# BMS_Master_eTable_RevC3.net
KiCad netlist of a schematic drawn in EAGLE
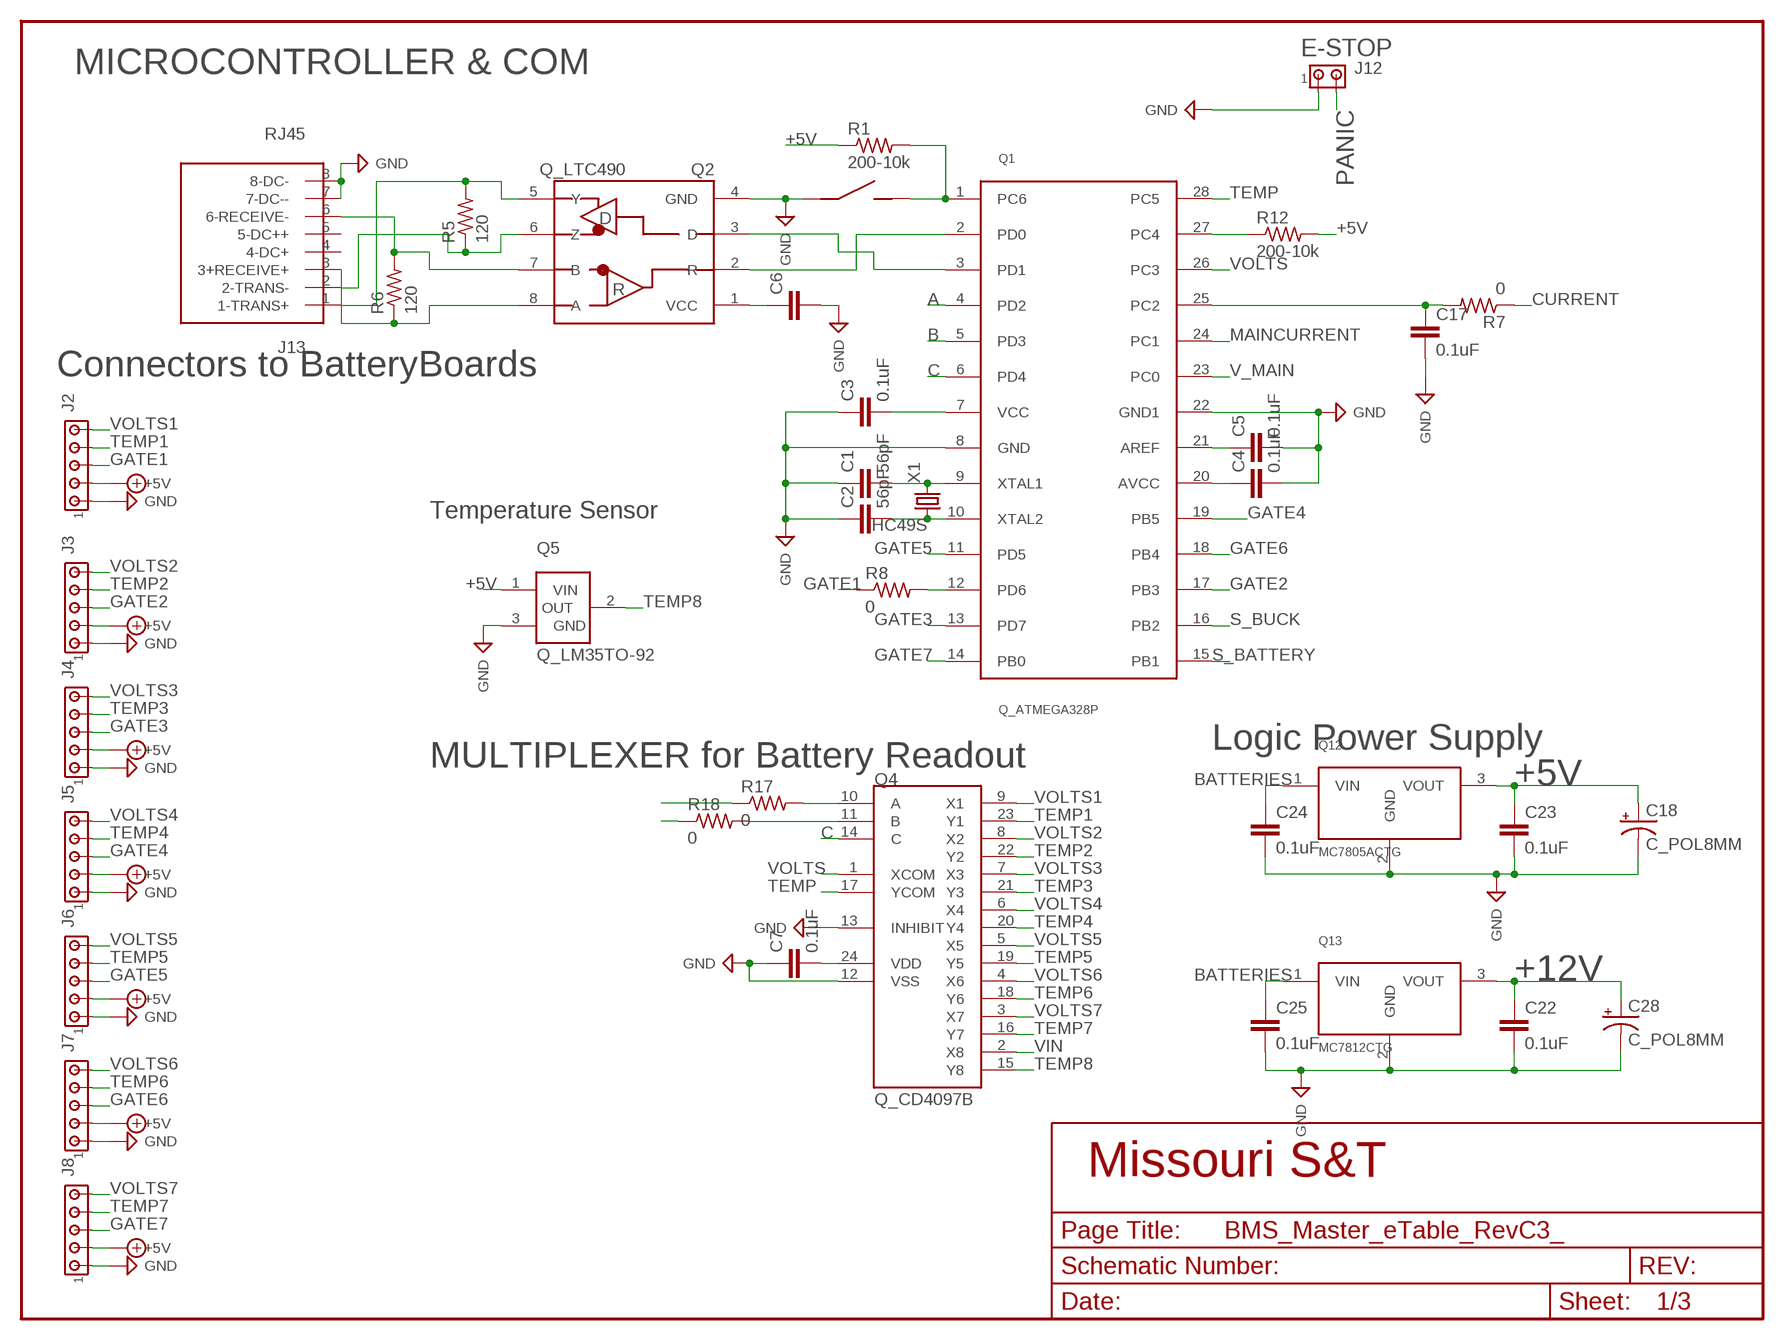
[diagram p0: schematic, sheet 1]
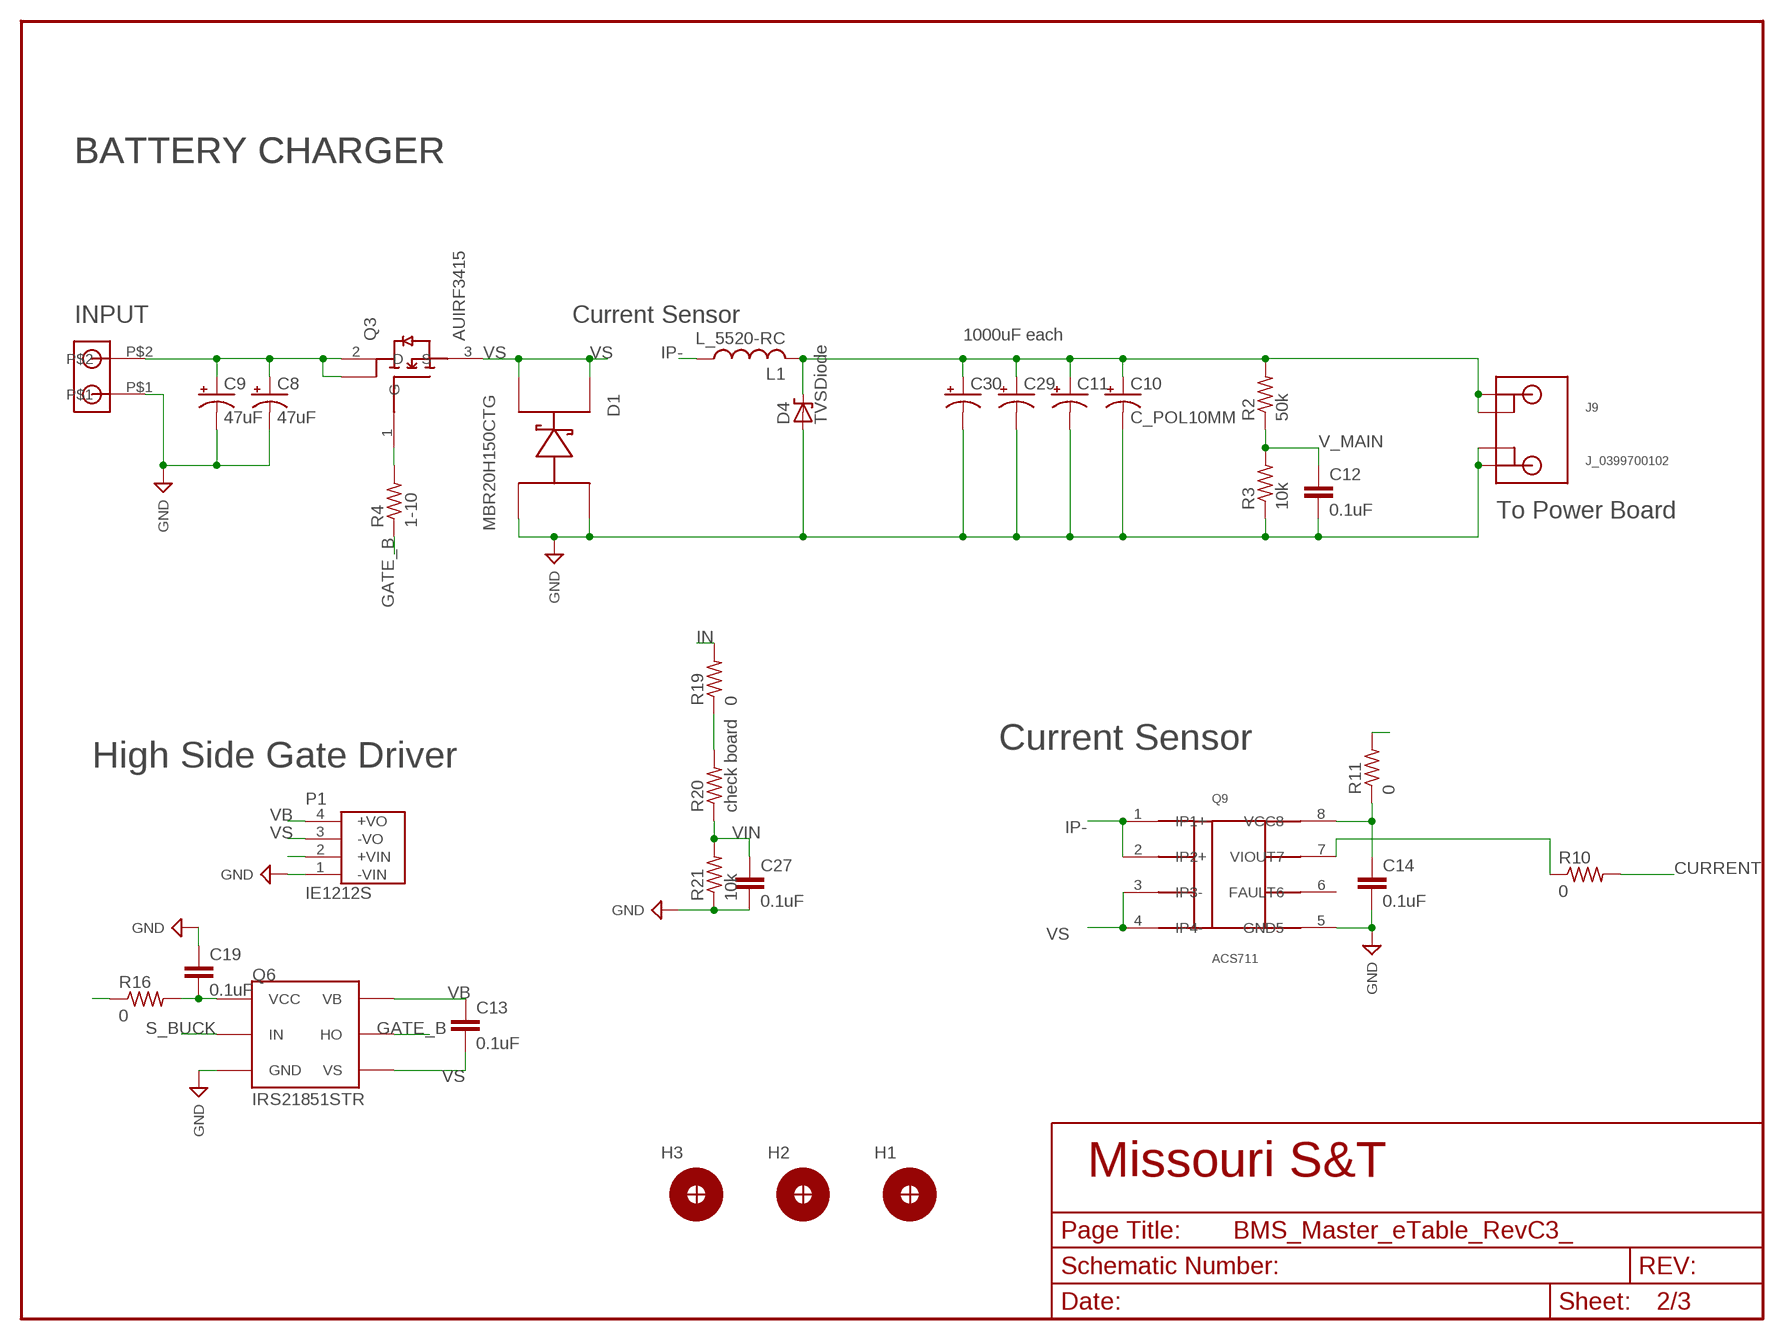
[diagram p1: schematic, sheet 2]
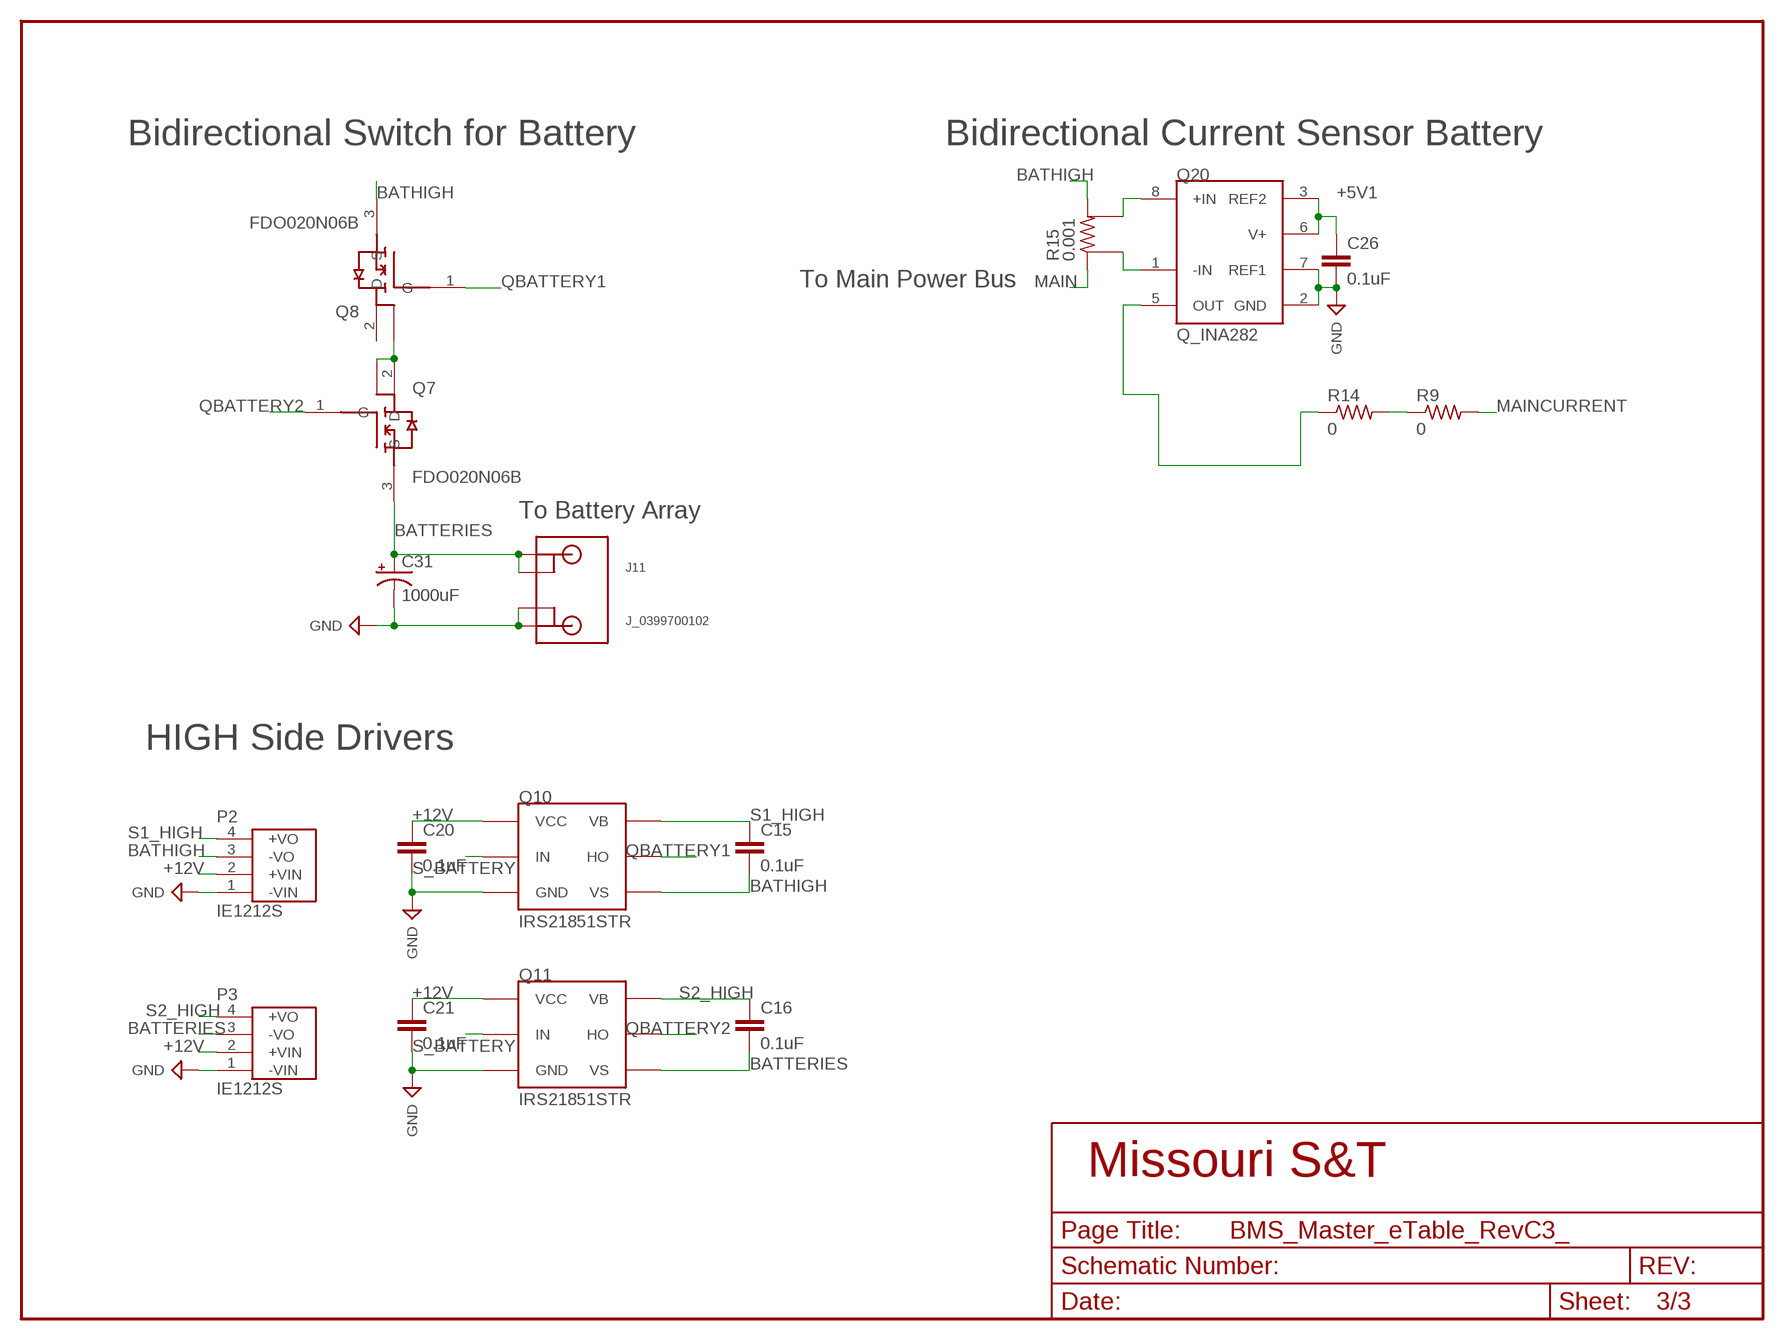
[diagram p2: schematic, sheet 3]

(export (version "E")
  (design (tool "Eeschema 10.0.6"))
  (components
    (comp (ref "C15")
      (value "0.1uF")
      (footprint "eagle-import:C_1206")
      (libsource (lib "eagle-import") (part "C_CAP_1206"))
    )
    (comp (ref "C16")
      (value "0.1uF")
      (footprint "eagle-import:C_1206")
      (libsource (lib "eagle-import") (part "C_CAP_1206"))
    )
    (comp (ref "C20")
      (value "0.1uF")
      (footprint "eagle-import:C_1206")
      (libsource (lib "eagle-import") (part "C_CAP_1206"))
    )
    (comp (ref "C21")
      (value "0.1uF")
      (footprint "eagle-import:C_1206")
      (libsource (lib "eagle-import") (part "C_CAP_1206"))
    )
    (comp (ref "C26")
      (value "0.1uF")
      (footprint "eagle-import:C_1206")
      (libsource (lib "eagle-import") (part "C_CAP_1206"))
    )
    (comp (ref "C31")
      (value "1000uF")
      (footprint "eagle-import:C_10MM")
      (libsource (lib "eagle-import") (part "C_POL10MM"))
    )
    (comp (ref "J11")
      (value "J_0399700102")
      (footprint "eagle-import:J_2CONHC")
      (libsource (lib "eagle-import") (part "J_0399700102"))
    )
    (comp (ref "P2")
      (value "IE1212S")
      (footprint "eagle-import:TME1215S")
      (libsource (lib "eagle-import") (part "TME1215S"))
    )
    (comp (ref "P3")
      (value "IE1212S")
      (footprint "eagle-import:TME1215S")
      (libsource (lib "eagle-import") (part "TME1215S"))
    )
    (comp (ref "Q7")
      (value "FDO020N06B")
      (footprint "eagle-import:TO-220-FLAT")
      (libsource (lib "eagle-import") (part "Q_CSD18532KCSPCB"))
    )
    (comp (ref "Q8")
      (value "FDO020N06B")
      (footprint "eagle-import:TO-220-FLAT")
      (libsource (lib "eagle-import") (part "Q_CSD18532KCSPCB"))
    )
    (comp (ref "Q10")
      (value "IRS21851STR")
      (footprint "eagle-import:SOIC8")
      (libsource (lib "eagle-import") (part "Q_IRS21851STR"))
    )
    (comp (ref "Q11")
      (value "IRS21851STR")
      (footprint "eagle-import:SOIC8")
      (libsource (lib "eagle-import") (part "Q_IRS21851STR"))
    )
    (comp (ref "Q20")
      (value "Q_INA282")
      (footprint "eagle-import:SOIC8")
      (libsource (lib "eagle-import") (part "Q_INA28"))
    )
    (comp (ref "R9")
      (value "0")
      (footprint "eagle-import:R_1_4W")
      (libsource (lib "eagle-import") (part "R_1/4W"))
    )
    (comp (ref "R14")
      (value "0")
      (footprint "eagle-import:R_1_4W")
      (libsource (lib "eagle-import") (part "R_1/4W"))
    )
    (comp (ref "R15")
      (value "0.001")
      (footprint "eagle-import:R_FC4L")
      (libsource (lib "eagle-import") (part "R_FC4L110R001JER"))
    )
    (comp (ref "C8")
      (value "47uF")
      (footprint "eagle-import:C_10MM")
      (libsource (lib "eagle-import") (part "C_POL10MM"))
    )
    (comp (ref "C9")
      (value "47uF")
      (footprint "eagle-import:C_10MM")
      (libsource (lib "eagle-import") (part "C_POL10MM"))
    )
    (comp (ref "C10")
      (value "C_POL10MM")
      (footprint "eagle-import:C_10MM")
      (libsource (lib "eagle-import") (part "C_POL10MM"))
    )
    (comp (ref "C11")
      (value "C_POL10MM")
      (footprint "eagle-import:C_10MM")
      (libsource (lib "eagle-import") (part "C_POL10MM"))
    )
    (comp (ref "C12")
      (value "0.1uF")
      (footprint "eagle-import:C_1206")
      (libsource (lib "eagle-import") (part "C_CAP_1206"))
    )
    (comp (ref "C13")
      (value "0.1uF")
      (footprint "eagle-import:C_1206")
      (libsource (lib "eagle-import") (part "C_CAP_1206"))
    )
    (comp (ref "C14")
      (value "0.1uF")
      (footprint "eagle-import:C_1206")
      (libsource (lib "eagle-import") (part "C_CAP_1206"))
    )
    (comp (ref "C19")
      (value "0.1uF")
      (footprint "eagle-import:C_1206")
      (libsource (lib "eagle-import") (part "C_CAP_1206"))
    )
    (comp (ref "C27")
      (value "0.1uF")
      (footprint "eagle-import:C_1206")
      (libsource (lib "eagle-import") (part "C_CAP_1206"))
    )
    (comp (ref "C29")
      (value "C_POL10MM")
      (footprint "eagle-import:C_10MM")
      (libsource (lib "eagle-import") (part "C_POL10MM"))
    )
    (comp (ref "C30")
      (value "C_POL10MM")
      (footprint "eagle-import:C_10MM")
      (libsource (lib "eagle-import") (part "C_POL10MM"))
    )
    (comp (ref "D1")
      (value "MBR20H150CTG")
      (footprint "eagle-import:TO-220-FLAT")
      (libsource (lib "eagle-import") (part "D_MBR20H150CTG"))
    )
    (comp (ref "D4")
      (value "TVSDiode")
      (footprint "eagle-import:DIODE_D3.5MM_LS15.24MM")
      (libsource (lib "eagle-import") (part "D_1.5KE480A_D3.5MM_LS15.24MM"))
    )
    (comp (ref "H1")
      (value "H_MNTHOLE_#6")
      (footprint "eagle-import:H_MNTHOLE_#6")
      (libsource (lib "eagle-import") (part "H_MNTHOLE_#6"))
    )
    (comp (ref "H2")
      (value "H_MNTHOLE_#6")
      (footprint "eagle-import:H_MNTHOLE_#6")
      (libsource (lib "eagle-import") (part "H_MNTHOLE_#6"))
    )
    (comp (ref "H3")
      (value "H_MNTHOLE_#6")
      (footprint "eagle-import:H_MNTHOLE_#6")
      (libsource (lib "eagle-import") (part "H_MNTHOLE_#6"))
    )
    (comp (ref "J9")
      (value "J_0399700102")
      (footprint "eagle-import:J_2CONHC")
      (libsource (lib "eagle-import") (part "J_0399700102"))
    )
    (comp (ref "J10")
      (value "J_1546074-2")
      (footprint "eagle-import:THERM_BLOCK_2")
      (libsource (lib "eagle-import") (part "J_1546074-2"))
    )
    (comp (ref "L1")
      (value "L_5520-RC")
      (footprint "eagle-import:L_5520-RC")
      (libsource (lib "eagle-import") (part "L_5520-RC"))
    )
    (comp (ref "P1")
      (value "IE1212S")
      (footprint "eagle-import:TME1215S")
      (libsource (lib "eagle-import") (part "TME1215S"))
    )
    (comp (ref "Q3")
      (value "AUIRF3415")
      (footprint "eagle-import:TO-220-FLAT")
      (libsource (lib "eagle-import") (part "Q_CSD18532KCSPCB"))
    )
    (comp (ref "Q6")
      (value "IRS21851STR")
      (footprint "eagle-import:SOIC8")
      (libsource (lib "eagle-import") (part "Q_IRS21851STR"))
    )
    (comp (ref "Q9")
      (value "ACS711")
      (footprint "eagle-import:Q_SO8")
      (libsource (lib "eagle-import") (part "Q_SO8ACS711"))
    )
    (comp (ref "R2")
      (value "50k")
      (footprint "eagle-import:R_1_4W")
      (libsource (lib "eagle-import") (part "R_1/4W"))
    )
    (comp (ref "R3")
      (value "10k")
      (footprint "eagle-import:R_1206")
      (libsource (lib "eagle-import") (part "R_RES_1206"))
    )
    (comp (ref "R4")
      (value "1-10")
      (footprint "eagle-import:R_1206")
      (libsource (lib "eagle-import") (part "Lib_Passive - Copy_R_RES_1206"))
    )
    (comp (ref "R10")
      (value "0")
      (footprint "eagle-import:R_1_4W")
      (libsource (lib "eagle-import") (part "R_1/4W"))
    )
    (comp (ref "R11")
      (value "0")
      (footprint "eagle-import:R_1_4W")
      (libsource (lib "eagle-import") (part "R_1/4W"))
    )
    (comp (ref "R16")
      (value "0")
      (footprint "eagle-import:R_1_4W")
      (libsource (lib "eagle-import") (part "R_1/4W"))
    )
    (comp (ref "R19")
      (value "0")
      (footprint "eagle-import:R_1_4W")
      (libsource (lib "eagle-import") (part "R_1/4W"))
    )
    (comp (ref "R20")
      (value "check board")
      (footprint "eagle-import:R_1_4W")
      (libsource (lib "eagle-import") (part "R_1/4W"))
    )
    (comp (ref "R21")
      (value "10k")
      (footprint "eagle-import:R_1206")
      (libsource (lib "eagle-import") (part "R_RES_1206"))
    )
    (comp (ref "C1")
      (value "56pF")
      (footprint "eagle-import:C_1206")
      (libsource (lib "eagle-import") (part "C_CAP_1206"))
    )
    (comp (ref "C2")
      (value "56pF")
      (footprint "eagle-import:C_1206")
      (libsource (lib "eagle-import") (part "C_CAP_1206"))
    )
    (comp (ref "C3")
      (value "0.1uF")
      (footprint "eagle-import:C_1206")
      (libsource (lib "eagle-import") (part "C_CAP_1206"))
    )
    (comp (ref "C4")
      (value "0.1uF")
      (footprint "eagle-import:C_1206")
      (libsource (lib "eagle-import") (part "C_CAP_1206"))
    )
    (comp (ref "C5")
      (value "0.1uF")
      (footprint "eagle-import:C_1206")
      (libsource (lib "eagle-import") (part "C_CAP_1206"))
    )
    (comp (ref "C6")
      (value "C_CAP_1206")
      (footprint "eagle-import:C_1206")
      (libsource (lib "eagle-import") (part "C_CAP_1206"))
    )
    (comp (ref "C7")
      (value "0.1uF")
      (footprint "eagle-import:C_1206")
      (libsource (lib "eagle-import") (part "C_CAP_1206"))
    )
    (comp (ref "C17")
      (value "0.1uF")
      (footprint "eagle-import:C_1206")
      (libsource (lib "eagle-import") (part "C_CAP_1206"))
    )
    (comp (ref "C18")
      (value "C_POL8MM")
      (footprint "eagle-import:C_8MM")
      (libsource (lib "eagle-import") (part "C_POL8MM"))
    )
    (comp (ref "C22")
      (value "0.1uF")
      (footprint "eagle-import:C_1206")
      (libsource (lib "eagle-import") (part "C_CAP_1206"))
    )
    (comp (ref "C23")
      (value "0.1uF")
      (footprint "eagle-import:C_1206")
      (libsource (lib "eagle-import") (part "C_CAP_1206"))
    )
    (comp (ref "C24")
      (value "0.1uF")
      (footprint "eagle-import:C_1206")
      (libsource (lib "eagle-import") (part "C_CAP_1206"))
    )
    (comp (ref "C25")
      (value "0.1uF")
      (footprint "eagle-import:C_1206")
      (libsource (lib "eagle-import") (part "C_CAP_1206"))
    )
    (comp (ref "C28")
      (value "C_POL8MM")
      (footprint "eagle-import:C_8MM")
      (libsource (lib "eagle-import") (part "C_POL8MM"))
    )
    (comp (ref "J1")
      (value "J_MC32857")
      (footprint "eagle-import:J_TOGGLE")
      (libsource (lib "eagle-import") (part "J_MC32857"))
    )
    (comp (ref "J2")
      (value "J_MTA5P_100")
      (footprint "eagle-import:J_MTA100_5P")
      (libsource (lib "eagle-import") (part "J_MTA5P_100"))
    )
    (comp (ref "J3")
      (value "J_MTA5P_100")
      (footprint "eagle-import:J_MTA100_5P")
      (libsource (lib "eagle-import") (part "J_MTA5P_100"))
    )
    (comp (ref "J4")
      (value "J_MTA5P_100")
      (footprint "eagle-import:J_MTA100_5P")
      (libsource (lib "eagle-import") (part "J_MTA5P_100"))
    )
    (comp (ref "J5")
      (value "J_MTA5P_100")
      (footprint "eagle-import:J_MTA100_5P")
      (libsource (lib "eagle-import") (part "J_MTA5P_100"))
    )
    (comp (ref "J6")
      (value "J_MTA5P_100")
      (footprint "eagle-import:J_MTA100_5P")
      (libsource (lib "eagle-import") (part "J_MTA5P_100"))
    )
    (comp (ref "J7")
      (value "J_MTA5P_100")
      (footprint "eagle-import:J_MTA100_5P")
      (libsource (lib "eagle-import") (part "J_MTA5P_100"))
    )
    (comp (ref "J8")
      (value "J_MTA5P_100")
      (footprint "eagle-import:J_MTA100_5P")
      (libsource (lib "eagle-import") (part "J_MTA5P_100"))
    )
    (comp (ref "J12")
      (value "J_MTA2P_100")
      (footprint "eagle-import:J_MTA100_2P")
      (libsource (lib "eagle-import") (part "J_MTA2P_100"))
    )
    (comp (ref "J13")
      (value "RJ45")
      (footprint "eagle-import:RJ45-CAT5E")
      (libsource (lib "eagle-import") (part "RJ45"))
    )
    (comp (ref "Q1")
      (value "Q_ATMEGA328P")
      (footprint "eagle-import:DIP28")
      (libsource (lib "eagle-import") (part "Q_ATMEGA328P"))
    )
    (comp (ref "Q2")
      (value "Q_LTC490")
      (footprint "eagle-import:DIP8")
      (libsource (lib "eagle-import") (part "Q_LTC490"))
    )
    (comp (ref "Q4")
      (value "Q_CD4097B")
      (footprint "eagle-import:WDIP24")
      (libsource (lib "eagle-import") (part "Q_CD4067BRIGHT"))
    )
    (comp (ref "Q5")
      (value "Q_LM35TO-92")
      (footprint "eagle-import:TO-92-3")
      (libsource (lib "eagle-import") (part "Q_LM35TO-92"))
    )
    (comp (ref "Q12")
      (value "MC7805ACTG")
      (footprint "eagle-import:TO-220")
      (libsource (lib "eagle-import") (part "Q_LDO"))
    )
    (comp (ref "Q13")
      (value "MC7812CTG")
      (footprint "eagle-import:TO-220")
      (libsource (lib "eagle-import") (part "Q_LDO"))
    )
    (comp (ref "R1")
      (value "200-10k")
      (footprint "eagle-import:R_1206")
      (libsource (lib "eagle-import") (part "R_RES_1206"))
    )
    (comp (ref "R5")
      (value "120")
      (footprint "eagle-import:R_1206")
      (libsource (lib "eagle-import") (part "Lib_Passive - Copy_R_RES_1206"))
    )
    (comp (ref "R6")
      (value "120")
      (footprint "eagle-import:R_1206")
      (libsource (lib "eagle-import") (part "Lib_Passive - Copy_R_RES_1206"))
    )
    (comp (ref "R7")
      (value "0")
      (footprint "eagle-import:R_1_4W")
      (libsource (lib "eagle-import") (part "R_1/4W"))
    )
    (comp (ref "R8")
      (value "0")
      (footprint "eagle-import:R_1_4W")
      (libsource (lib "eagle-import") (part "R_1/4W"))
    )
    (comp (ref "R12")
      (value "200-10k")
      (footprint "eagle-import:R_0805")
      (libsource (lib "eagle-import") (part "R_RES_0805"))
    )
    (comp (ref "R17")
      (value "0")
      (footprint "eagle-import:R_1_4W")
      (libsource (lib "eagle-import") (part "R_1/4W"))
    )
    (comp (ref "R18")
      (value "0")
      (footprint "eagle-import:R_1_4W")
      (libsource (lib "eagle-import") (part "R_1/4W"))
    )
    (comp (ref "X1")
      (value "HC49S")
      (footprint "eagle-import:HC-49")
      (libsource (lib "eagle-import") (part "X_HC49SCRYSTAL"))
    )
  )
  (nets
    (net (code "1") (name "+5V") (class "Default")
      (node (ref "C18") (pin "+") (pinfunction "+_+") (pintype "passive"))
      (node (ref "C23") (pin "1") (pinfunction "1_1") (pintype "passive"))
      (node (ref "C3") (pin "2") (pinfunction "2_2") (pintype "passive"))
      (node (ref "C4") (pin "1") (pinfunction "1_1") (pintype "passive"))
      (node (ref "C6") (pin "1") (pinfunction "1_1") (pintype "passive"))
      (node (ref "C7") (pin "2") (pinfunction "2_2") (pintype "passive"))
      (node (ref "J2") (pin "2") (pinfunction "2_2") (pintype "passive"))
      (node (ref "J3") (pin "2") (pinfunction "2_2") (pintype "passive"))
      (node (ref "J4") (pin "2") (pinfunction "2_2") (pintype "passive"))
      (node (ref "J5") (pin "2") (pinfunction "2_2") (pintype "passive"))
      (node (ref "J6") (pin "2") (pinfunction "2_2") (pintype "passive"))
      (node (ref "J7") (pin "2") (pinfunction "2_2") (pintype "passive"))
      (node (ref "J8") (pin "2") (pinfunction "2_2") (pintype "passive"))
      (node (ref "Q1") (pin "20") (pinfunction "AVCC_20") (pintype "bidirectional"))
      (node (ref "Q1") (pin "7") (pinfunction "VCC_7") (pintype "bidirectional"))
      (node (ref "Q12") (pin "3") (pinfunction "VOUT_3") (pintype "bidirectional"))
      (node (ref "Q2") (pin "1") (pinfunction "VCC_1") (pintype "bidirectional"))
      (node (ref "Q4") (pin "24") (pinfunction "VDD_24") (pintype "bidirectional"))
      (node (ref "Q5") (pin "1") (pinfunction "VIN_1") (pintype "bidirectional"))
      (node (ref "R1") (pin "1") (pinfunction "1_1") (pintype "passive"))
      (node (ref "R11") (pin "2") (pinfunction "2_2") (pintype "passive"))
      (node (ref "R12") (pin "2") (pinfunction "2_2") (pintype "passive"))
    )
    (net (code "2") (name "+5V1") (class "Default")
      (node (ref "C14") (pin "1") (pinfunction "1_1") (pintype "passive"))
      (node (ref "C26") (pin "1") (pinfunction "1_1") (pintype "passive"))
      (node (ref "Q20") (pin "3") (pinfunction "REF2_3") (pintype "bidirectional"))
      (node (ref "Q20") (pin "6") (pinfunction "V+_6") (pintype "bidirectional"))
      (node (ref "Q9") (pin "8") (pinfunction "VCC8_8") (pintype "bidirectional"))
      (node (ref "R11") (pin "1") (pinfunction "1_1") (pintype "passive"))
    )
    (net (code "3") (name "+12V") (class "Default")
      (node (ref "C20") (pin "1") (pinfunction "1_1") (pintype "passive"))
      (node (ref "C21") (pin "1") (pinfunction "1_1") (pintype "passive"))
      (node (ref "C22") (pin "1") (pinfunction "1_1") (pintype "passive"))
      (node (ref "C28") (pin "+") (pinfunction "+_+") (pintype "passive"))
      (node (ref "P2") (pin "2") (pinfunction "+VIN_2") (pintype "input"))
      (node (ref "P3") (pin "2") (pinfunction "+VIN_2") (pintype "input"))
      (node (ref "Q10") (pin "1") (pinfunction "VCC_1") (pintype "bidirectional"))
      (node (ref "Q11") (pin "1") (pinfunction "VCC_1") (pintype "bidirectional"))
      (node (ref "Q13") (pin "3") (pinfunction "VOUT_3") (pintype "bidirectional"))
      (node (ref "R16") (pin "1") (pinfunction "1_1") (pintype "passive"))
    )
    (net (code "4") (name "+12V1") (class "Default")
      (node (ref "C19") (pin "2") (pinfunction "2_2") (pintype "passive"))
      (node (ref "P1") (pin "2") (pinfunction "+VIN_2") (pintype "input"))
      (node (ref "Q6") (pin "1") (pinfunction "VCC_1") (pintype "bidirectional"))
      (node (ref "R16") (pin "2") (pinfunction "2_2") (pintype "passive"))
    )
    (net (code "5") (name "A") (class "Default")
      (node (ref "Q1") (pin "4") (pinfunction "PD2_4") (pintype "bidirectional"))
      (node (ref "R17") (pin "1") (pinfunction "1_1") (pintype "passive"))
    )
    (net (code "6") (name "B") (class "Default")
      (node (ref "Q1") (pin "5") (pinfunction "PD3_5") (pintype "bidirectional"))
      (node (ref "R18") (pin "1") (pinfunction "1_1") (pintype "passive"))
    )
    (net (code "7") (name "BATHIGH") (class "Default")
      (node (ref "C15") (pin "2") (pinfunction "2_2") (pintype "passive"))
      (node (ref "P2") (pin "3") (pinfunction "-VO_3") (pintype "output"))
      (node (ref "Q10") (pin "6") (pinfunction "VS_6") (pintype "bidirectional"))
      (node (ref "Q8") (pin "3") (pinfunction "S_3") (pintype "bidirectional"))
      (node (ref "R15") (pin "2") (pinfunction "2_2") (pintype "passive"))
    )
    (net (code "8") (name "BATTERIES") (class "Default")
      (node (ref "C16") (pin "2") (pinfunction "2_2") (pintype "passive"))
      (node (ref "C24") (pin "1") (pinfunction "1_1") (pintype "passive"))
      (node (ref "C25") (pin "1") (pinfunction "1_1") (pintype "passive"))
      (node (ref "C31") (pin "P$1") (pinfunction "+_P$1") (pintype "passive"))
      (node (ref "J11") (pin "PIN1-1") (pinfunction "1-1_PIN1-1") (pintype "bidirectional"))
      (node (ref "J11") (pin "PIN1-2") (pinfunction "1-2_PIN1-2") (pintype "bidirectional"))
      (node (ref "P3") (pin "3") (pinfunction "-VO_3") (pintype "output"))
      (node (ref "Q11") (pin "6") (pinfunction "VS_6") (pintype "bidirectional"))
      (node (ref "Q12") (pin "1") (pinfunction "VIN_1") (pintype "bidirectional"))
      (node (ref "Q13") (pin "1") (pinfunction "VIN_1") (pintype "bidirectional"))
      (node (ref "Q7") (pin "3") (pinfunction "S_3") (pintype "bidirectional"))
    )
    (net (code "9") (name "C") (class "Default")
      (node (ref "Q1") (pin "6") (pinfunction "PD4_6") (pintype "bidirectional"))
      (node (ref "Q4") (pin "14") (pinfunction "C_14") (pintype "bidirectional"))
    )
    (net (code "10") (name "CURRENT") (class "Default")
      (node (ref "R10") (pin "2") (pinfunction "2_2") (pintype "passive"))
      (node (ref "R7") (pin "1") (pinfunction "1_1") (pintype "passive"))
    )
    (net (code "11") (name "GATE1") (class "Default")
      (node (ref "J2") (pin "3") (pinfunction "3_3") (pintype "passive"))
      (node (ref "R8") (pin "1") (pinfunction "1_1") (pintype "passive"))
    )
    (net (code "12") (name "GATE2") (class "Default")
      (node (ref "J3") (pin "3") (pinfunction "3_3") (pintype "passive"))
      (node (ref "Q1") (pin "17") (pinfunction "PB3_17") (pintype "bidirectional"))
    )
    (net (code "13") (name "GATE3") (class "Default")
      (node (ref "J4") (pin "3") (pinfunction "3_3") (pintype "passive"))
      (node (ref "Q1") (pin "13") (pinfunction "PD7_13") (pintype "bidirectional"))
    )
    (net (code "14") (name "GATE4") (class "Default")
      (node (ref "J5") (pin "3") (pinfunction "3_3") (pintype "passive"))
      (node (ref "Q1") (pin "19") (pinfunction "PB5_19") (pintype "bidirectional"))
    )
    (net (code "15") (name "GATE5") (class "Default")
      (node (ref "J6") (pin "3") (pinfunction "3_3") (pintype "passive"))
      (node (ref "Q1") (pin "11") (pinfunction "PD5_11") (pintype "bidirectional"))
    )
    (net (code "16") (name "GATE6") (class "Default")
      (node (ref "J7") (pin "3") (pinfunction "3_3") (pintype "passive"))
      (node (ref "Q1") (pin "18") (pinfunction "PB4_18") (pintype "bidirectional"))
    )
    (net (code "17") (name "GATE7") (class "Default")
      (node (ref "J8") (pin "3") (pinfunction "3_3") (pintype "passive"))
      (node (ref "Q1") (pin "14") (pinfunction "PB0_14") (pintype "bidirectional"))
    )
    (net (code "18") (name "GATE_B") (class "Default")
      (node (ref "Q6") (pin "7") (pinfunction "HO_7") (pintype "bidirectional"))
      (node (ref "R4") (pin "1") (pinfunction "1_1") (pintype "passive"))
    )
    (net (code "19") (name "GND") (class "Default")
      (node (ref "C1") (pin "1") (pinfunction "1_1") (pintype "passive"))
      (node (ref "C10") (pin "P$2") (pinfunction "-_P$2") (pintype "passive"))
      (node (ref "C11") (pin "P$2") (pinfunction "-_P$2") (pintype "passive"))
      (node (ref "C12") (pin "2") (pinfunction "2_2") (pintype "passive"))
      (node (ref "C14") (pin "2") (pinfunction "2_2") (pintype "passive"))
      (node (ref "C17") (pin "2") (pinfunction "2_2") (pintype "passive"))
      (node (ref "C18") (pin "-") (pinfunction "-_-") (pintype "passive"))
      (node (ref "C19") (pin "1") (pinfunction "1_1") (pintype "passive"))
      (node (ref "C2") (pin "1") (pinfunction "1_1") (pintype "passive"))
      (node (ref "C20") (pin "2") (pinfunction "2_2") (pintype "passive"))
      (node (ref "C21") (pin "2") (pinfunction "2_2") (pintype "passive"))
      (node (ref "C22") (pin "2") (pinfunction "2_2") (pintype "passive"))
      (node (ref "C23") (pin "2") (pinfunction "2_2") (pintype "passive"))
      (node (ref "C24") (pin "2") (pinfunction "2_2") (pintype "passive"))
      (node (ref "C25") (pin "2") (pinfunction "2_2") (pintype "passive"))
      (node (ref "C26") (pin "2") (pinfunction "2_2") (pintype "passive"))
      (node (ref "C27") (pin "2") (pinfunction "2_2") (pintype "passive"))
      (node (ref "C28") (pin "-") (pinfunction "-_-") (pintype "passive"))
      (node (ref "C29") (pin "P$2") (pinfunction "-_P$2") (pintype "passive"))
      (node (ref "C3") (pin "1") (pinfunction "1_1") (pintype "passive"))
      (node (ref "C30") (pin "P$2") (pinfunction "-_P$2") (pintype "passive"))
      (node (ref "C31") (pin "P$2") (pinfunction "-_P$2") (pintype "passive"))
      (node (ref "C4") (pin "2") (pinfunction "2_2") (pintype "passive"))
      (node (ref "C5") (pin "2") (pinfunction "2_2") (pintype "passive"))
      (node (ref "C6") (pin "2") (pinfunction "2_2") (pintype "passive"))
      (node (ref "C7") (pin "1") (pinfunction "1_1") (pintype "passive"))
      (node (ref "C8") (pin "P$2") (pinfunction "-_P$2") (pintype "passive"))
      (node (ref "C9") (pin "P$2") (pinfunction "-_P$2") (pintype "passive"))
      (node (ref "D1") (pin "1") (pinfunction "A1_1") (pintype "bidirectional"))
      (node (ref "D1") (pin "3") (pinfunction "A2_3") (pintype "bidirectional"))
      (node (ref "D4") (pin "A") (pinfunction "A_A") (pintype "passive"))
      (node (ref "J1") (pin "P$1") (pinfunction "1_P$1") (pintype "bidirectional"))
      (node (ref "J10") (pin "P$1") (pinfunction "P$1_P$1") (pintype "bidirectional"))
      (node (ref "J11") (pin "PIN2-1") (pinfunction "2-1_PIN2-1") (pintype "bidirectional"))
      (node (ref "J11") (pin "PIN2-2") (pinfunction "2-2_PIN2-2") (pintype "bidirectional"))
      (node (ref "J12") (pin "1") (pinfunction "1_1") (pintype "passive"))
      (node (ref "J13") (pin "7") (pinfunction "7-DC--_7") (pintype "bidirectional"))
      (node (ref "J13") (pin "8") (pinfunction "8-DC-_8") (pintype "bidirectional"))
      (node (ref "J2") (pin "1") (pinfunction "1_1") (pintype "passive"))
      (node (ref "J3") (pin "1") (pinfunction "1_1") (pintype "passive"))
      (node (ref "J4") (pin "1") (pinfunction "1_1") (pintype "passive"))
      (node (ref "J5") (pin "1") (pinfunction "1_1") (pintype "passive"))
      (node (ref "J6") (pin "1") (pinfunction "1_1") (pintype "passive"))
      (node (ref "J7") (pin "1") (pinfunction "1_1") (pintype "passive"))
      (node (ref "J8") (pin "1") (pinfunction "1_1") (pintype "passive"))
      (node (ref "J9") (pin "PIN2-1") (pinfunction "2-1_PIN2-1") (pintype "bidirectional"))
      (node (ref "J9") (pin "PIN2-2") (pinfunction "2-2_PIN2-2") (pintype "bidirectional"))
      (node (ref "P1") (pin "1") (pinfunction "-VIN_1") (pintype "input"))
      (node (ref "P2") (pin "1") (pinfunction "-VIN_1") (pintype "input"))
      (node (ref "P3") (pin "1") (pinfunction "-VIN_1") (pintype "input"))
      (node (ref "Q1") (pin "22") (pinfunction "GND1_22") (pintype "bidirectional"))
      (node (ref "Q1") (pin "8") (pinfunction "GND_8") (pintype "bidirectional"))
      (node (ref "Q10") (pin "4") (pinfunction "GND_4") (pintype "bidirectional"))
      (node (ref "Q11") (pin "4") (pinfunction "GND_4") (pintype "bidirectional"))
      (node (ref "Q12") (pin "2") (pinfunction "GND_2") (pintype "bidirectional"))
      (node (ref "Q13") (pin "2") (pinfunction "GND_2") (pintype "bidirectional"))
      (node (ref "Q2") (pin "4") (pinfunction "GND_4") (pintype "bidirectional"))
      (node (ref "Q20") (pin "2") (pinfunction "GND_2") (pintype "bidirectional"))
      (node (ref "Q20") (pin "7") (pinfunction "REF1_7") (pintype "bidirectional"))
      (node (ref "Q4") (pin "12") (pinfunction "VSS_12") (pintype "bidirectional"))
      (node (ref "Q4") (pin "13") (pinfunction "INHIBIT_13") (pintype "bidirectional"))
      (node (ref "Q5") (pin "3") (pinfunction "GND_3") (pintype "bidirectional"))
      (node (ref "Q6") (pin "4") (pinfunction "GND_4") (pintype "bidirectional"))
      (node (ref "Q9") (pin "5") (pinfunction "GND5_5") (pintype "bidirectional"))
      (node (ref "R21") (pin "1") (pinfunction "1_1") (pintype "passive"))
      (node (ref "R3") (pin "1") (pinfunction "1_1") (pintype "passive"))
    )
    (net (code "20") (name "IN") (class "Default")
      (node (ref "C8") (pin "P$1") (pinfunction "+_P$1") (pintype "passive"))
      (node (ref "C9") (pin "P$1") (pinfunction "+_P$1") (pintype "passive"))
      (node (ref "J10") (pin "P$2") (pinfunction "P$2_P$2") (pintype "bidirectional"))
      (node (ref "Q3") (pin "2") (pinfunction "D_2") (pintype "bidirectional"))
      (node (ref "Q3") (pin "4") (pinfunction "P$1_4") (pintype "bidirectional"))
      (node (ref "R19") (pin "2") (pinfunction "2_2") (pintype "passive"))
    )
    (net (code "21") (name "IP-") (class "Default")
      (node (ref "L1") (pin "1") (pinfunction "1_1") (pintype "passive"))
      (node (ref "Q9") (pin "1") (pinfunction "IP1+_1") (pintype "bidirectional"))
      (node (ref "Q9") (pin "2") (pinfunction "IP2+_2") (pintype "bidirectional"))
    )
    (net (code "22") (name "MAIN") (class "Default")
      (node (ref "C10") (pin "P$1") (pinfunction "+_P$1") (pintype "passive"))
      (node (ref "C11") (pin "P$1") (pinfunction "+_P$1") (pintype "passive"))
      (node (ref "C29") (pin "P$1") (pinfunction "+_P$1") (pintype "passive"))
      (node (ref "C30") (pin "P$1") (pinfunction "+_P$1") (pintype "passive"))
      (node (ref "D4") (pin "C") (pinfunction "K_C") (pintype "passive"))
      (node (ref "J9") (pin "PIN1-1") (pinfunction "1-1_PIN1-1") (pintype "bidirectional"))
      (node (ref "J9") (pin "PIN1-2") (pinfunction "1-2_PIN1-2") (pintype "bidirectional"))
      (node (ref "L1") (pin "2") (pinfunction "2_2") (pintype "passive"))
      (node (ref "R15") (pin "1") (pinfunction "1_1") (pintype "passive"))
      (node (ref "R2") (pin "2") (pinfunction "2_2") (pintype "passive"))
    )
    (net (code "23") (name "MAINCURRENT") (class "Default")
      (node (ref "Q1") (pin "24") (pinfunction "PC1_24") (pintype "bidirectional"))
      (node (ref "R9") (pin "2") (pinfunction "2_2") (pintype "passive"))
    )
    (net (code "24") (name "Net-(J1-2)") (class "Default")
      (node (ref "J1") (pin "P$2") (pinfunction "2_P$2") (pintype "bidirectional"))
      (node (ref "Q1") (pin "1") (pinfunction "PC6_1") (pintype "bidirectional"))
      (node (ref "R1") (pin "2") (pinfunction "2_2") (pintype "passive"))
    )
    (net (code "25") (name "Net-(J13-1-TRANS+)") (class "Default")
      (node (ref "J13") (pin "1") (pinfunction "1-TRANS+_1") (pintype "bidirectional"))
      (node (ref "Q2") (pin "5") (pinfunction "Y_5") (pintype "bidirectional"))
      (node (ref "R5") (pin "2") (pinfunction "2_2") (pintype "passive"))
    )
    (net (code "26") (name "Net-(J13-2-TRANS-)") (class "Default")
      (node (ref "J13") (pin "2") (pinfunction "2-TRANS-_2") (pintype "bidirectional"))
      (node (ref "Q2") (pin "6") (pinfunction "Z_6") (pintype "bidirectional"))
      (node (ref "R5") (pin "1") (pinfunction "1_1") (pintype "passive"))
    )
    (net (code "27") (name "Net-(J13-3+RECEIVE+)") (class "Default")
      (node (ref "J13") (pin "3") (pinfunction "3+RECEIVE+_3") (pintype "bidirectional"))
      (node (ref "Q2") (pin "8") (pinfunction "A_8") (pintype "bidirectional"))
      (node (ref "R6") (pin "1") (pinfunction "1_1") (pintype "passive"))
    )
    (net (code "28") (name "Net-(J13-6-RECEIVE-)") (class "Default")
      (node (ref "J13") (pin "6") (pinfunction "6-RECEIVE-_6") (pintype "bidirectional"))
      (node (ref "Q2") (pin "7") (pinfunction "B_7") (pintype "bidirectional"))
      (node (ref "R6") (pin "2") (pinfunction "2_2") (pintype "passive"))
    )
    (net (code "29") (name "Net-(Q1-AREF)") (class "Default")
      (node (ref "C5") (pin "1") (pinfunction "1_1") (pintype "passive"))
      (node (ref "Q1") (pin "21") (pinfunction "AREF_21") (pintype "bidirectional"))
    )
    (net (code "30") (name "Net-(Q1-PC2)") (class "Default")
      (node (ref "C17") (pin "1") (pinfunction "1_1") (pintype "passive"))
      (node (ref "Q1") (pin "25") (pinfunction "PC2_25") (pintype "bidirectional"))
      (node (ref "R7") (pin "2") (pinfunction "2_2") (pintype "passive"))
    )
    (net (code "31") (name "Net-(Q1-PD0)") (class "Default")
      (node (ref "Q1") (pin "2") (pinfunction "PD0_2") (pintype "bidirectional"))
      (node (ref "Q2") (pin "2") (pinfunction "R_2") (pintype "bidirectional"))
    )
    (net (code "32") (name "Net-(Q1-PD1)") (class "Default")
      (node (ref "Q1") (pin "3") (pinfunction "PD1_3") (pintype "bidirectional"))
      (node (ref "Q2") (pin "3") (pinfunction "D_3") (pintype "bidirectional"))
    )
    (net (code "33") (name "Net-(Q1-PD6)") (class "Default")
      (node (ref "Q1") (pin "12") (pinfunction "PD6_12") (pintype "bidirectional"))
      (node (ref "R8") (pin "2") (pinfunction "2_2") (pintype "passive"))
    )
    (net (code "34") (name "Net-(Q1-XTAL1)") (class "Default")
      (node (ref "C1") (pin "2") (pinfunction "2_2") (pintype "passive"))
      (node (ref "Q1") (pin "9") (pinfunction "XTAL1_9") (pintype "bidirectional"))
      (node (ref "X1") (pin "P$2") (pinfunction "2_P$2") (pintype "passive"))
    )
    (net (code "35") (name "Net-(Q1-XTAL2)") (class "Default")
      (node (ref "C2") (pin "2") (pinfunction "2_2") (pintype "passive"))
      (node (ref "Q1") (pin "10") (pinfunction "XTAL2_10") (pintype "bidirectional"))
      (node (ref "X1") (pin "P$1") (pinfunction "1_P$1") (pintype "passive"))
    )
    (net (code "36") (name "Net-(Q3-G)") (class "Default")
      (node (ref "Q3") (pin "1") (pinfunction "G_1") (pintype "bidirectional"))
      (node (ref "R4") (pin "2") (pinfunction "2_2") (pintype "passive"))
    )
    (net (code "37") (name "Net-(Q4-A)") (class "Default")
      (node (ref "Q4") (pin "10") (pinfunction "A_10") (pintype "bidirectional"))
      (node (ref "R17") (pin "2") (pinfunction "2_2") (pintype "passive"))
    )
    (net (code "38") (name "Net-(Q4-B)") (class "Default")
      (node (ref "Q4") (pin "11") (pinfunction "B_11") (pintype "bidirectional"))
      (node (ref "R18") (pin "2") (pinfunction "2_2") (pintype "passive"))
    )
    (net (code "39") (name "Net-(Q7-D)") (class "Default")
      (node (ref "Q7") (pin "2") (pinfunction "D_2") (pintype "bidirectional"))
      (node (ref "Q7") (pin "4") (pinfunction "P$1_4") (pintype "bidirectional"))
      (node (ref "Q8") (pin "4") (pinfunction "P$1_4") (pintype "bidirectional"))
    )
    (net (code "40") (name "Net-(Q9-VIOUT7)") (class "Default")
      (node (ref "Q9") (pin "7") (pinfunction "VIOUT7_7") (pintype "bidirectional"))
      (node (ref "R10") (pin "1") (pinfunction "1_1") (pintype "passive"))
    )
    (net (code "41") (name "Net-(Q20-+IN)") (class "Default")
      (node (ref "Q20") (pin "8") (pinfunction "+IN_8") (pintype "bidirectional"))
      (node (ref "R15") (pin "SENSE2") (pinfunction "SENSE2_SENSE2") (pintype "bidirectional"))
    )
    (net (code "42") (name "Net-(Q20--IN)") (class "Default")
      (node (ref "Q20") (pin "1") (pinfunction "-IN_1") (pintype "bidirectional"))
      (node (ref "R15") (pin "SENSE1") (pinfunction "SENSE1_SENSE1") (pintype "bidirectional"))
    )
    (net (code "43") (name "Net-(Q20-OUT)") (class "Default")
      (node (ref "Q20") (pin "5") (pinfunction "OUT_5") (pintype "bidirectional"))
      (node (ref "R14") (pin "1") (pinfunction "1_1") (pintype "passive"))
    )
    (net (code "44") (name "Net-(R14-Pad2)") (class "Default")
      (node (ref "R14") (pin "2") (pinfunction "2_2") (pintype "passive"))
      (node (ref "R9") (pin "1") (pinfunction "1_1") (pintype "passive"))
    )
    (net (code "45") (name "Net-(R19-Pad1)") (class "Default")
      (node (ref "R19") (pin "1") (pinfunction "1_1") (pintype "passive"))
      (node (ref "R20") (pin "2") (pinfunction "2_2") (pintype "passive"))
    )
    (net (code "46") (name "PANIC") (class "Default")
      (node (ref "J12") (pin "2") (pinfunction "2_2") (pintype "passive"))
      (node (ref "Q1") (pin "27") (pinfunction "PC4_27") (pintype "bidirectional"))
      (node (ref "R12") (pin "1") (pinfunction "1_1") (pintype "passive"))
    )
    (net (code "47") (name "QBATTERY1") (class "Default")
      (node (ref "Q10") (pin "7") (pinfunction "HO_7") (pintype "bidirectional"))
      (node (ref "Q8") (pin "1") (pinfunction "G_1") (pintype "bidirectional"))
    )
    (net (code "48") (name "QBATTERY2") (class "Default")
      (node (ref "Q11") (pin "7") (pinfunction "HO_7") (pintype "bidirectional"))
      (node (ref "Q7") (pin "1") (pinfunction "G_1") (pintype "bidirectional"))
    )
    (net (code "49") (name "S1_HIGH") (class "Default")
      (node (ref "C15") (pin "1") (pinfunction "1_1") (pintype "passive"))
      (node (ref "P2") (pin "4") (pinfunction "+VO_4") (pintype "output"))
      (node (ref "Q10") (pin "8") (pinfunction "VB_8") (pintype "bidirectional"))
    )
    (net (code "50") (name "S2_HIGH") (class "Default")
      (node (ref "C16") (pin "1") (pinfunction "1_1") (pintype "passive"))
      (node (ref "P3") (pin "4") (pinfunction "+VO_4") (pintype "output"))
      (node (ref "Q11") (pin "8") (pinfunction "VB_8") (pintype "bidirectional"))
    )
    (net (code "51") (name "S_BATTERY") (class "Default")
      (node (ref "Q1") (pin "15") (pinfunction "PB1_15") (pintype "bidirectional"))
      (node (ref "Q10") (pin "2") (pinfunction "IN_2") (pintype "bidirectional"))
      (node (ref "Q11") (pin "2") (pinfunction "IN_2") (pintype "bidirectional"))
    )
    (net (code "52") (name "S_BUCK") (class "Default")
      (node (ref "Q1") (pin "16") (pinfunction "PB2_16") (pintype "bidirectional"))
      (node (ref "Q6") (pin "2") (pinfunction "IN_2") (pintype "bidirectional"))
    )
    (net (code "53") (name "TEMP") (class "Default")
      (node (ref "Q1") (pin "28") (pinfunction "PC5_28") (pintype "bidirectional"))
      (node (ref "Q4") (pin "17") (pinfunction "YCOM_17") (pintype "bidirectional"))
    )
    (net (code "54") (name "TEMP1") (class "Default")
      (node (ref "J2") (pin "4") (pinfunction "4_4") (pintype "passive"))
      (node (ref "Q4") (pin "23") (pinfunction "Y1_23") (pintype "bidirectional"))
    )
    (net (code "55") (name "TEMP2") (class "Default")
      (node (ref "J3") (pin "4") (pinfunction "4_4") (pintype "passive"))
      (node (ref "Q4") (pin "22") (pinfunction "Y2_22") (pintype "bidirectional"))
    )
    (net (code "56") (name "TEMP3") (class "Default")
      (node (ref "J4") (pin "4") (pinfunction "4_4") (pintype "passive"))
      (node (ref "Q4") (pin "21") (pinfunction "Y3_21") (pintype "bidirectional"))
    )
    (net (code "57") (name "TEMP4") (class "Default")
      (node (ref "J5") (pin "4") (pinfunction "4_4") (pintype "passive"))
      (node (ref "Q4") (pin "20") (pinfunction "Y4_20") (pintype "bidirectional"))
    )
    (net (code "58") (name "TEMP5") (class "Default")
      (node (ref "J6") (pin "4") (pinfunction "4_4") (pintype "passive"))
      (node (ref "Q4") (pin "19") (pinfunction "Y5_19") (pintype "bidirectional"))
    )
    (net (code "59") (name "TEMP6") (class "Default")
      (node (ref "J7") (pin "4") (pinfunction "4_4") (pintype "passive"))
      (node (ref "Q4") (pin "18") (pinfunction "Y6_18") (pintype "bidirectional"))
    )
    (net (code "60") (name "TEMP7") (class "Default")
      (node (ref "J8") (pin "4") (pinfunction "4_4") (pintype "passive"))
      (node (ref "Q4") (pin "16") (pinfunction "Y7_16") (pintype "bidirectional"))
    )
    (net (code "61") (name "TEMP8") (class "Default")
      (node (ref "Q4") (pin "15") (pinfunction "Y8_15") (pintype "bidirectional"))
      (node (ref "Q5") (pin "2") (pinfunction "OUT_2") (pintype "bidirectional"))
    )
    (net (code "62") (name "VB") (class "Default")
      (node (ref "C13") (pin "1") (pinfunction "1_1") (pintype "passive"))
      (node (ref "P1") (pin "4") (pinfunction "+VO_4") (pintype "output"))
      (node (ref "Q6") (pin "8") (pinfunction "VB_8") (pintype "bidirectional"))
    )
    (net (code "63") (name "VIN") (class "Default")
      (node (ref "C27") (pin "1") (pinfunction "1_1") (pintype "passive"))
      (node (ref "Q4") (pin "2") (pinfunction "X8_2") (pintype "bidirectional"))
      (node (ref "R20") (pin "1") (pinfunction "1_1") (pintype "passive"))
      (node (ref "R21") (pin "2") (pinfunction "2_2") (pintype "passive"))
    )
    (net (code "64") (name "VOLTS") (class "Default")
      (node (ref "Q1") (pin "26") (pinfunction "PC3_26") (pintype "bidirectional"))
      (node (ref "Q4") (pin "1") (pinfunction "XCOM_1") (pintype "bidirectional"))
    )
    (net (code "65") (name "VOLTS1") (class "Default")
      (node (ref "J2") (pin "5") (pinfunction "5_5") (pintype "passive"))
      (node (ref "Q4") (pin "9") (pinfunction "X1_9") (pintype "bidirectional"))
    )
    (net (code "66") (name "VOLTS2") (class "Default")
      (node (ref "J3") (pin "5") (pinfunction "5_5") (pintype "passive"))
      (node (ref "Q4") (pin "8") (pinfunction "X2_8") (pintype "bidirectional"))
    )
    (net (code "67") (name "VOLTS3") (class "Default")
      (node (ref "J4") (pin "5") (pinfunction "5_5") (pintype "passive"))
      (node (ref "Q4") (pin "7") (pinfunction "X3_7") (pintype "bidirectional"))
    )
    (net (code "68") (name "VOLTS4") (class "Default")
      (node (ref "J5") (pin "5") (pinfunction "5_5") (pintype "passive"))
      (node (ref "Q4") (pin "6") (pinfunction "X4_6") (pintype "bidirectional"))
    )
    (net (code "69") (name "VOLTS5") (class "Default")
      (node (ref "J6") (pin "5") (pinfunction "5_5") (pintype "passive"))
      (node (ref "Q4") (pin "5") (pinfunction "X5_5") (pintype "bidirectional"))
    )
    (net (code "70") (name "VOLTS6") (class "Default")
      (node (ref "J7") (pin "5") (pinfunction "5_5") (pintype "passive"))
      (node (ref "Q4") (pin "4") (pinfunction "X6_4") (pintype "bidirectional"))
    )
    (net (code "71") (name "VOLTS7") (class "Default")
      (node (ref "J8") (pin "5") (pinfunction "5_5") (pintype "passive"))
      (node (ref "Q4") (pin "3") (pinfunction "X7_3") (pintype "bidirectional"))
    )
    (net (code "72") (name "VS") (class "Default")
      (node (ref "C13") (pin "2") (pinfunction "2_2") (pintype "passive"))
      (node (ref "D1") (pin "2") (pinfunction "C1_2") (pintype "bidirectional"))
      (node (ref "D1") (pin "4") (pinfunction "C2_4") (pintype "bidirectional"))
      (node (ref "P1") (pin "3") (pinfunction "-VO_3") (pintype "output"))
      (node (ref "Q3") (pin "3") (pinfunction "S_3") (pintype "bidirectional"))
      (node (ref "Q6") (pin "6") (pinfunction "VS_6") (pintype "bidirectional"))
      (node (ref "Q9") (pin "3") (pinfunction "IP3-_3") (pintype "bidirectional"))
      (node (ref "Q9") (pin "4") (pinfunction "IP4-_4") (pintype "bidirectional"))
    )
    (net (code "73") (name "V_MAIN") (class "Default")
      (node (ref "C12") (pin "1") (pinfunction "1_1") (pintype "passive"))
      (node (ref "Q1") (pin "23") (pinfunction "PC0_23") (pintype "bidirectional"))
      (node (ref "R2") (pin "1") (pinfunction "1_1") (pintype "passive"))
      (node (ref "R3") (pin "2") (pinfunction "2_2") (pintype "passive"))
    )
    (net (code "74") (name "unconnected-(H1-Pad1)") (class "Default")
      (node (ref "H1") (pin "1") (pinfunction "1_1") (pintype "passive"))
    )
    (net (code "75") (name "unconnected-(H2-Pad1)") (class "Default")
      (node (ref "H2") (pin "1") (pinfunction "1_1") (pintype "passive"))
    )
    (net (code "76") (name "unconnected-(H3-Pad1)") (class "Default")
      (node (ref "H3") (pin "1") (pinfunction "1_1") (pintype "passive"))
    )
    (net (code "77") (name "unconnected-(J13-4-DC+-Pad4)") (class "Default")
      (node (ref "J13") (pin "4") (pinfunction "4-DC+_4") (pintype "bidirectional"))
    )
    (net (code "78") (name "unconnected-(J13-5-DC++-Pad5)") (class "Default")
      (node (ref "J13") (pin "5") (pinfunction "5-DC++_5") (pintype "bidirectional"))
    )
    (net (code "79") (name "unconnected-(Q8-D-Pad2)") (class "Default")
      (node (ref "Q8") (pin "2") (pinfunction "D_2") (pintype "bidirectional"))
    )
    (net (code "80") (name "unconnected-(Q9-FAULT6-Pad6)") (class "Default")
      (node (ref "Q9") (pin "6") (pinfunction "FAULT6_6") (pintype "bidirectional"))
    )
  )
)
